# BMP390.net
KiCad netlist of a schematic drawn in Altium Designer
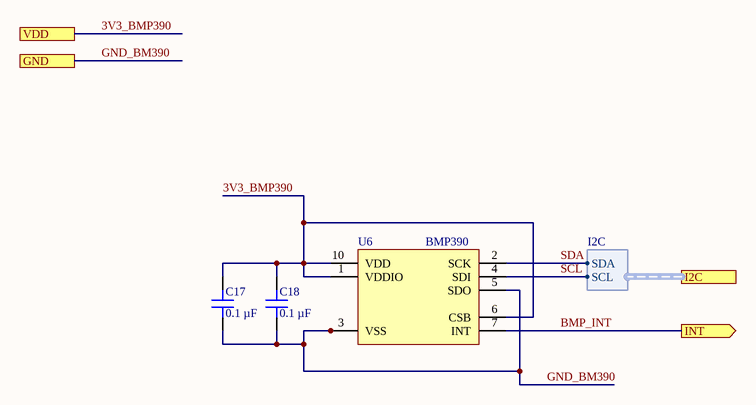
[diagram p0: BMP390.SchDoc]

(export (version "E")
  (design (tool "Eeschema 10.0.6"))
  (components
    (comp (ref "C17")
      (value "0.1 µF")
      (footprint "CAP 0402_1005")
      (description "CAP CER 0.1UF 16V X7R 0402")
      (fields (field (name "PART NUMBER") "C0402C104K4RACAUTO") (field (name "MANUFACTURER") "KEMET"))
      (libsource (lib "Celestial Altium Library - altium_library") (part "Capacitor"))
    )
    (comp (ref "C18")
      (value "0.1 µF")
      (footprint "CAP 0402_1005")
      (description "CAP CER 0.1UF 16V X7R 0402")
      (fields (field (name "PART NUMBER") "C0402C104K4RACAUTO") (field (name "MANUFACTURER") "KEMET"))
      (libsource (lib "Celestial Altium Library - altium_library") (part "Capacitor"))
    )
    (comp (ref "U6")
      (value "BMP390")
      (footprint "BMP390L")
      (description "Altimeter")
      (libsource (lib "IC") (part "BMP390"))
    )
  )
  (nets
    (net (code "2") (name "/3V3_BMP390") (class "Default")
      (node (ref "C17") (pin "2") (pinfunction "2_2") (pintype "passive"))
      (node (ref "C18") (pin "2") (pinfunction "2_2") (pintype "passive"))
      (node (ref "U6") (pin "1") (pinfunction "VDDIO_1") (pintype "passive"))
      (node (ref "U6") (pin "10") (pinfunction "VDD_10") (pintype "passive"))
      (node (ref "U6") (pin "6") (pinfunction "CSB_6") (pintype "passive"))
    )
    (net (code "3") (name "/BMP_INT") (class "Default")
      (node (ref "U6") (pin "7") (pinfunction "INT_7") (pintype "passive"))
    )
    (net (code "4") (name "/GND_BM390") (class "Default")
      (node (ref "C17") (pin "1") (pinfunction "1_1") (pintype "passive"))
      (node (ref "C18") (pin "1") (pinfunction "1_1") (pintype "passive"))
      (node (ref "U6") (pin "3") (pinfunction "VSS_3") (pintype "passive"))
      (node (ref "U6") (pin "5") (pinfunction "SDO_5") (pintype "passive"))
      (node (ref "U6") (pin "8") (pinfunction "VSS_8") (pintype "passive"))
      (node (ref "U6") (pin "9") (pinfunction "VSS_9") (pintype "passive"))
    )
    (net (code "5") (name "/SCL") (class "Default")
      (node (ref "U6") (pin "4") (pinfunction "SDI_4") (pintype "passive"))
    )
    (net (code "6") (name "/SDA") (class "Default")
      (node (ref "U6") (pin "2") (pinfunction "SCK_2") (pintype "passive"))
    )
  )
)
